# MCU.net
KiCad netlist of a schematic drawn in Altium Designer
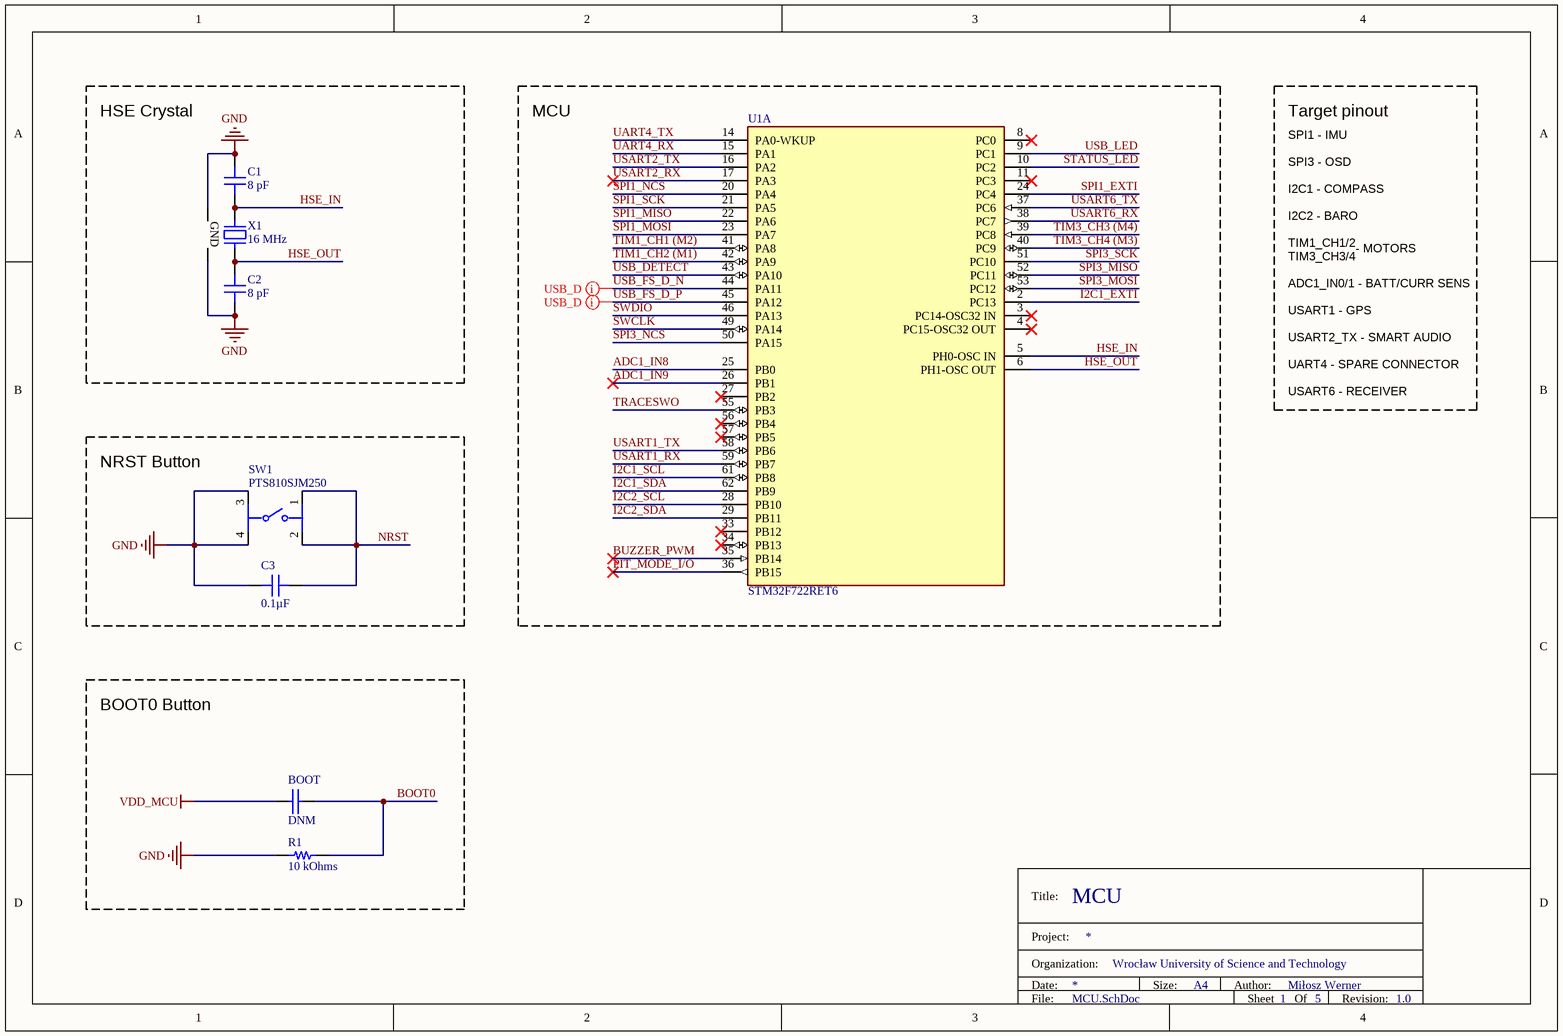
[diagram p0: MCU.SchDoc]

(export (version "E")
  (design (tool "Eeschema 10.0.6"))
  (components
    (comp (ref "BOOT")
      (value "DNM")
      (footprint "NO_BOM:C0603_DNM")
      (description "CAP 0603 DO NOT MOUNT")
      (libsource (lib "NO_BOM") (part "CAP_0603_DNM"))
    )
    (comp (ref "C1")
      (value "8 pF")
      (footprint "CAP 0603_1608")
      (description "CAP CER 8PF 50V C0G 0603")
      (fields
        (field (name "PART NUMBER") "CGA3E2C0G1H080D080AA")
        (field (name "MANUFACTURER") "TDK Corporation")
      )
      (libsource (lib "Celestial Altium Library - altium_library") (part "Capacitor"))
    )
    (comp (ref "C2")
      (value "8 pF")
      (footprint "CAP 0603_1608")
      (description "CAP CER 8PF 50V C0G 0603")
      (fields
        (field (name "PART NUMBER") "CGA3E2C0G1H080D080AA")
        (field (name "MANUFACTURER") "TDK Corporation")
      )
      (libsource (lib "Celestial Altium Library - altium_library") (part "Capacitor"))
    )
    (comp (ref "C3")
      (value "0.1µF")
      (footprint "CAP 0603_1608")
      (description "CAP CER 0.1UF 25V X7R 0603")
      (fields (field (name "PART NUMBER") "06033C104JAT4A") (field (name "MANUFACTURER") "AVX Corporation"))
      (libsource (lib "Celestial Altium Library - altium_library") (part "Capacitor"))
    )
    (comp (ref "R1")
      (value "10 kOhms")
      (footprint "RES 0603_1608")
      (description "RES 10K OHM 0.1% 1/5W 0603")
      (fields
        (field (name "PART NUMBER") "RS73F1JTTD1002B")
        (field (name "MANUFACTURER") "KOA Speer Electronics, Inc.")
      )
      (libsource (lib "Celestial Altium Library - altium_library") (part "Resistor"))
    )
    (comp (ref "SW1")
      (value "PTS810SJM250")
      (footprint "FP-PTS810SJM250SMTRLFS-MFG")
      (description "SWITCH TACTILE SPST-NO 0.05A 16V")
      (libsource (lib "Altium Content Vault") (part "1adf0dd01260c80cf25a44bfd6b99ba"))
    )
    (comp (ref "U1")
      (value "STM32F722RET6")
      (footprint "FP-LQFP64-5W-IPC_C")
      (description "IC MCU 32BIT 512KB FLASH 64LQFP")
      (libsource (lib "Altium Content Vault") (part "413d838e29415566e97646d24ea8a00"))
    )
    (comp (ref "X1")
      (value "16 MHz")
      (footprint "NDK NX3225GA")
      (description "CRYSTAL 16.0000MHZ 8PF SMD")
      (fields
        (field (name "PART NUMBER") "NX3225GA-16.000M-STD-CRG-2")
        (field (name "MANUFACTURER") "NDK America, Inc.")
      )
      (libsource (lib "Celestial Altium Library - altium_library") (part "NDK Crystal NX3225GA"))
    )
  )
  (nets
    (net (code "1") (name "/ADC1_IN8") (class "Default")
      (node (ref "U1") (pin "25") (pinfunction "PB0_25") (pintype "passive"))
    )
    (net (code "2") (name "/ADC1_IN9") (class "Default")
      (node (ref "U1") (pin "26") (pinfunction "PB1_26") (pintype "passive+no_connect"))
    )
    (net (code "3") (name "/BOOT0") (class "Default")
      (node (ref "BOOT") (pin "2") (pinfunction "2_2") (pintype "passive"))
      (node (ref "R1") (pin "2") (pinfunction "2_2") (pintype "passive"))
    )
    (net (code "4") (name "/BUZZER_PWM") (class "Default")
      (node (ref "U1") (pin "35") (pinfunction "PB14_35") (pintype "input+no_connect"))
    )
    (net (code "5") (name "/HSE_IN") (class "Default")
      (node (ref "C1") (pin "1") (pinfunction "1_1") (pintype "passive"))
      (node (ref "U1") (pin "5") (pinfunction "PH0-OSC_IN_5") (pintype "passive"))
      (node (ref "X1") (pin "1") (pinfunction "1_1") (pintype "passive"))
    )
    (net (code "6") (name "/HSE_OUT") (class "Default")
      (node (ref "C2") (pin "2") (pinfunction "2_2") (pintype "passive"))
      (node (ref "U1") (pin "6") (pinfunction "PH1-OSC_OUT_6") (pintype "passive"))
      (node (ref "X1") (pin "3") (pinfunction "3_3") (pintype "passive"))
    )
    (net (code "7") (name "/I2C1_EXTI") (class "Default")
      (node (ref "U1") (pin "2") (pinfunction "PC13_2") (pintype "passive"))
    )
    (net (code "8") (name "/I2C1_SCL") (class "Default")
      (node (ref "U1") (pin "61") (pinfunction "PB8_61") (pintype "bidirectional"))
    )
    (net (code "9") (name "/I2C1_SDA") (class "Default")
      (node (ref "U1") (pin "62") (pinfunction "PB9_62") (pintype "power_in"))
    )
    (net (code "10") (name "/I2C2_SCL") (class "Default")
      (node (ref "U1") (pin "28") (pinfunction "PB10_28") (pintype "passive"))
    )
    (net (code "11") (name "/I2C2_SDA") (class "Default")
      (node (ref "U1") (pin "29") (pinfunction "PB11_29") (pintype "passive"))
    )
    (net (code "12") (name "/NRST") (class "Default")
      (node (ref "C3") (pin "1") (pinfunction "1_1") (pintype "passive"))
      (node (ref "SW1") (pin "1") (pinfunction "1_1") (pintype "passive"))
      (node (ref "SW1") (pin "2") (pinfunction "2_2") (pintype "passive"))
    )
    (net (code "13") (name "/PIT_MODE_I{slash}O") (class "Default")
      (node (ref "U1") (pin "36") (pinfunction "PB15_36") (pintype "output+no_connect"))
    )
    (net (code "14") (name "/SPI1_EXTI") (class "Default")
      (node (ref "U1") (pin "24") (pinfunction "PC4_24") (pintype "passive"))
    )
    (net (code "15") (name "/SPI1_MISO") (class "Default")
      (node (ref "U1") (pin "22") (pinfunction "PA6_22") (pintype "passive"))
    )
    (net (code "16") (name "/SPI1_MOSI") (class "Default")
      (node (ref "U1") (pin "23") (pinfunction "PA7_23") (pintype "passive"))
    )
    (net (code "17") (name "/SPI1_NCS") (class "Default")
      (node (ref "U1") (pin "20") (pinfunction "PA4_20") (pintype "passive"))
    )
    (net (code "18") (name "/SPI1_SCK") (class "Default")
      (node (ref "U1") (pin "21") (pinfunction "PA5_21") (pintype "passive"))
    )
    (net (code "19") (name "/SPI3_MISO") (class "Default")
      (node (ref "U1") (pin "52") (pinfunction "PC11_52") (pintype "bidirectional"))
    )
    (net (code "20") (name "/SPI3_MOSI") (class "Default")
      (node (ref "U1") (pin "53") (pinfunction "PC12_53") (pintype "bidirectional"))
    )
    (net (code "21") (name "/SPI3_NCS") (class "Default")
      (node (ref "U1") (pin "50") (pinfunction "PA15_50") (pintype "power_in"))
    )
    (net (code "22") (name "/SPI3_SCK") (class "Default")
      (node (ref "U1") (pin "51") (pinfunction "PC10_51") (pintype "power_in"))
    )
    (net (code "23") (name "/STATUS_LED") (class "Default")
      (node (ref "U1") (pin "10") (pinfunction "PC2_10") (pintype "passive"))
    )
    (net (code "24") (name "/SWCLK") (class "Default")
      (node (ref "U1") (pin "49") (pinfunction "PA14_49") (pintype "bidirectional"))
    )
    (net (code "25") (name "/SWDIO") (class "Default")
      (node (ref "U1") (pin "46") (pinfunction "PA13_46") (pintype "passive"))
    )
    (net (code "26") (name "/TIM1_CH1 (M2)") (class "Default")
      (node (ref "U1") (pin "41") (pinfunction "PA8_41") (pintype "bidirectional"))
    )
    (net (code "27") (name "/TIM1_CH2 (M1)") (class "Default")
      (node (ref "U1") (pin "42") (pinfunction "PA9_42") (pintype "bidirectional"))
    )
    (net (code "28") (name "/TIM3_CH3 (M4)") (class "Default")
      (node (ref "U1") (pin "39") (pinfunction "PC8_39") (pintype "input"))
    )
    (net (code "29") (name "/TIM3_CH4 (M3)") (class "Default")
      (node (ref "U1") (pin "40") (pinfunction "PC9_40") (pintype "bidirectional"))
    )
    (net (code "30") (name "/TRACESWO") (class "Default")
      (node (ref "U1") (pin "55") (pinfunction "PB3_55") (pintype "bidirectional"))
    )
    (net (code "31") (name "/UART4_RX") (class "Default")
      (node (ref "U1") (pin "15") (pinfunction "PA1_15") (pintype "passive"))
    )
    (net (code "32") (name "/UART4_TX") (class "Default")
      (node (ref "U1") (pin "14") (pinfunction "PA0-WKUP_14") (pintype "passive"))
    )
    (net (code "33") (name "/USART1_RX") (class "Default")
      (node (ref "U1") (pin "59") (pinfunction "PB7_59") (pintype "bidirectional"))
    )
    (net (code "34") (name "/USART1_TX") (class "Default")
      (node (ref "U1") (pin "58") (pinfunction "PB6_58") (pintype "bidirectional"))
    )
    (net (code "35") (name "/USART2_RX") (class "Default")
      (node (ref "U1") (pin "17") (pinfunction "PA3_17") (pintype "passive+no_connect"))
    )
    (net (code "36") (name "/USART2_TX") (class "Default")
      (node (ref "U1") (pin "16") (pinfunction "PA2_16") (pintype "passive"))
    )
    (net (code "37") (name "/USART6_RX") (class "Default")
      (node (ref "U1") (pin "38") (pinfunction "PC7_38") (pintype "output"))
    )
    (net (code "38") (name "/USART6_TX") (class "Default")
      (node (ref "U1") (pin "37") (pinfunction "PC6_37") (pintype "input"))
    )
    (net (code "39") (name "/USB_DETECT") (class "Default")
      (node (ref "U1") (pin "43") (pinfunction "PA10_43") (pintype "bidirectional"))
    )
    (net (code "40") (name "/USB_FS_D_N") (class "Default")
      (node (ref "U1") (pin "44") (pinfunction "PA11_44") (pintype "power_in"))
    )
    (net (code "41") (name "/USB_FS_D_P") (class "Default")
      (node (ref "U1") (pin "45") (pinfunction "PA12_45") (pintype "power_in"))
    )
    (net (code "42") (name "/USB_LED") (class "Default")
      (node (ref "U1") (pin "9") (pinfunction "PC1_9") (pintype "passive"))
    )
    (net (code "43") (name "GND") (class "Default")
      (node (ref "C1") (pin "2") (pinfunction "2_2") (pintype "passive"))
      (node (ref "C2") (pin "1") (pinfunction "1_1") (pintype "passive"))
      (node (ref "C3") (pin "2") (pinfunction "2_2") (pintype "passive"))
      (node (ref "R1") (pin "1") (pinfunction "1_1") (pintype "passive"))
      (node (ref "SW1") (pin "3") (pinfunction "3_3") (pintype "passive"))
      (node (ref "SW1") (pin "4") (pinfunction "4_4") (pintype "passive"))
      (node (ref "X1") (pin "2") (pinfunction "GND_2") (pintype "passive"))
      (node (ref "X1") (pin "4") (pinfunction "GND_4") (pintype "passive"))
    )
    (net (code "44") (name "VDD_MCU") (class "Default")
      (node (ref "BOOT") (pin "1") (pinfunction "1_1") (pintype "passive"))
    )
    (net (code "45") (name "unconnected-(U1A-PB2-Pad27)") (class "Default")
      (node (ref "U1") (pin "27") (pinfunction "PB2_27") (pintype "passive+no_connect"))
    )
    (net (code "46") (name "unconnected-(U1A-PB4-Pad56)") (class "Default")
      (node (ref "U1") (pin "56") (pinfunction "PB4_56") (pintype "bidirectional+no_connect"))
    )
    (net (code "47") (name "unconnected-(U1A-PB5-Pad57)") (class "Default")
      (node (ref "U1") (pin "57") (pinfunction "PB5_57") (pintype "bidirectional+no_connect"))
    )
    (net (code "48") (name "unconnected-(U1A-PB12-Pad33)") (class "Default")
      (node (ref "U1") (pin "33") (pinfunction "PB12_33") (pintype "power_in+no_connect"))
    )
    (net (code "49") (name "unconnected-(U1A-PB13-Pad34)") (class "Default")
      (node (ref "U1") (pin "34") (pinfunction "PB13_34") (pintype "bidirectional+no_connect"))
    )
    (net (code "50") (name "unconnected-(U1A-PC0-Pad8)") (class "Default")
      (node (ref "U1") (pin "8") (pinfunction "PC0_8") (pintype "passive+no_connect"))
    )
    (net (code "51") (name "unconnected-(U1A-PC3-Pad11)") (class "Default")
      (node (ref "U1") (pin "11") (pinfunction "PC3_11") (pintype "passive+no_connect"))
    )
    (net (code "52") (name "unconnected-(U1A-PC14-OSC32_IN-Pad3)") (class "Default")
      (node (ref "U1") (pin "3") (pinfunction "PC14-OSC32_IN_3") (pintype "passive+no_connect"))
    )
    (net (code "53") (name "unconnected-(U1A-PC15-OSC32_OUT-Pad4)") (class "Default")
      (node (ref "U1") (pin "4") (pinfunction "PC15-OSC32_OUT_4") (pintype "passive+no_connect"))
    )
  )
)
